# User_Interface.net
KiCad netlist of a schematic drawn in Altium Designer
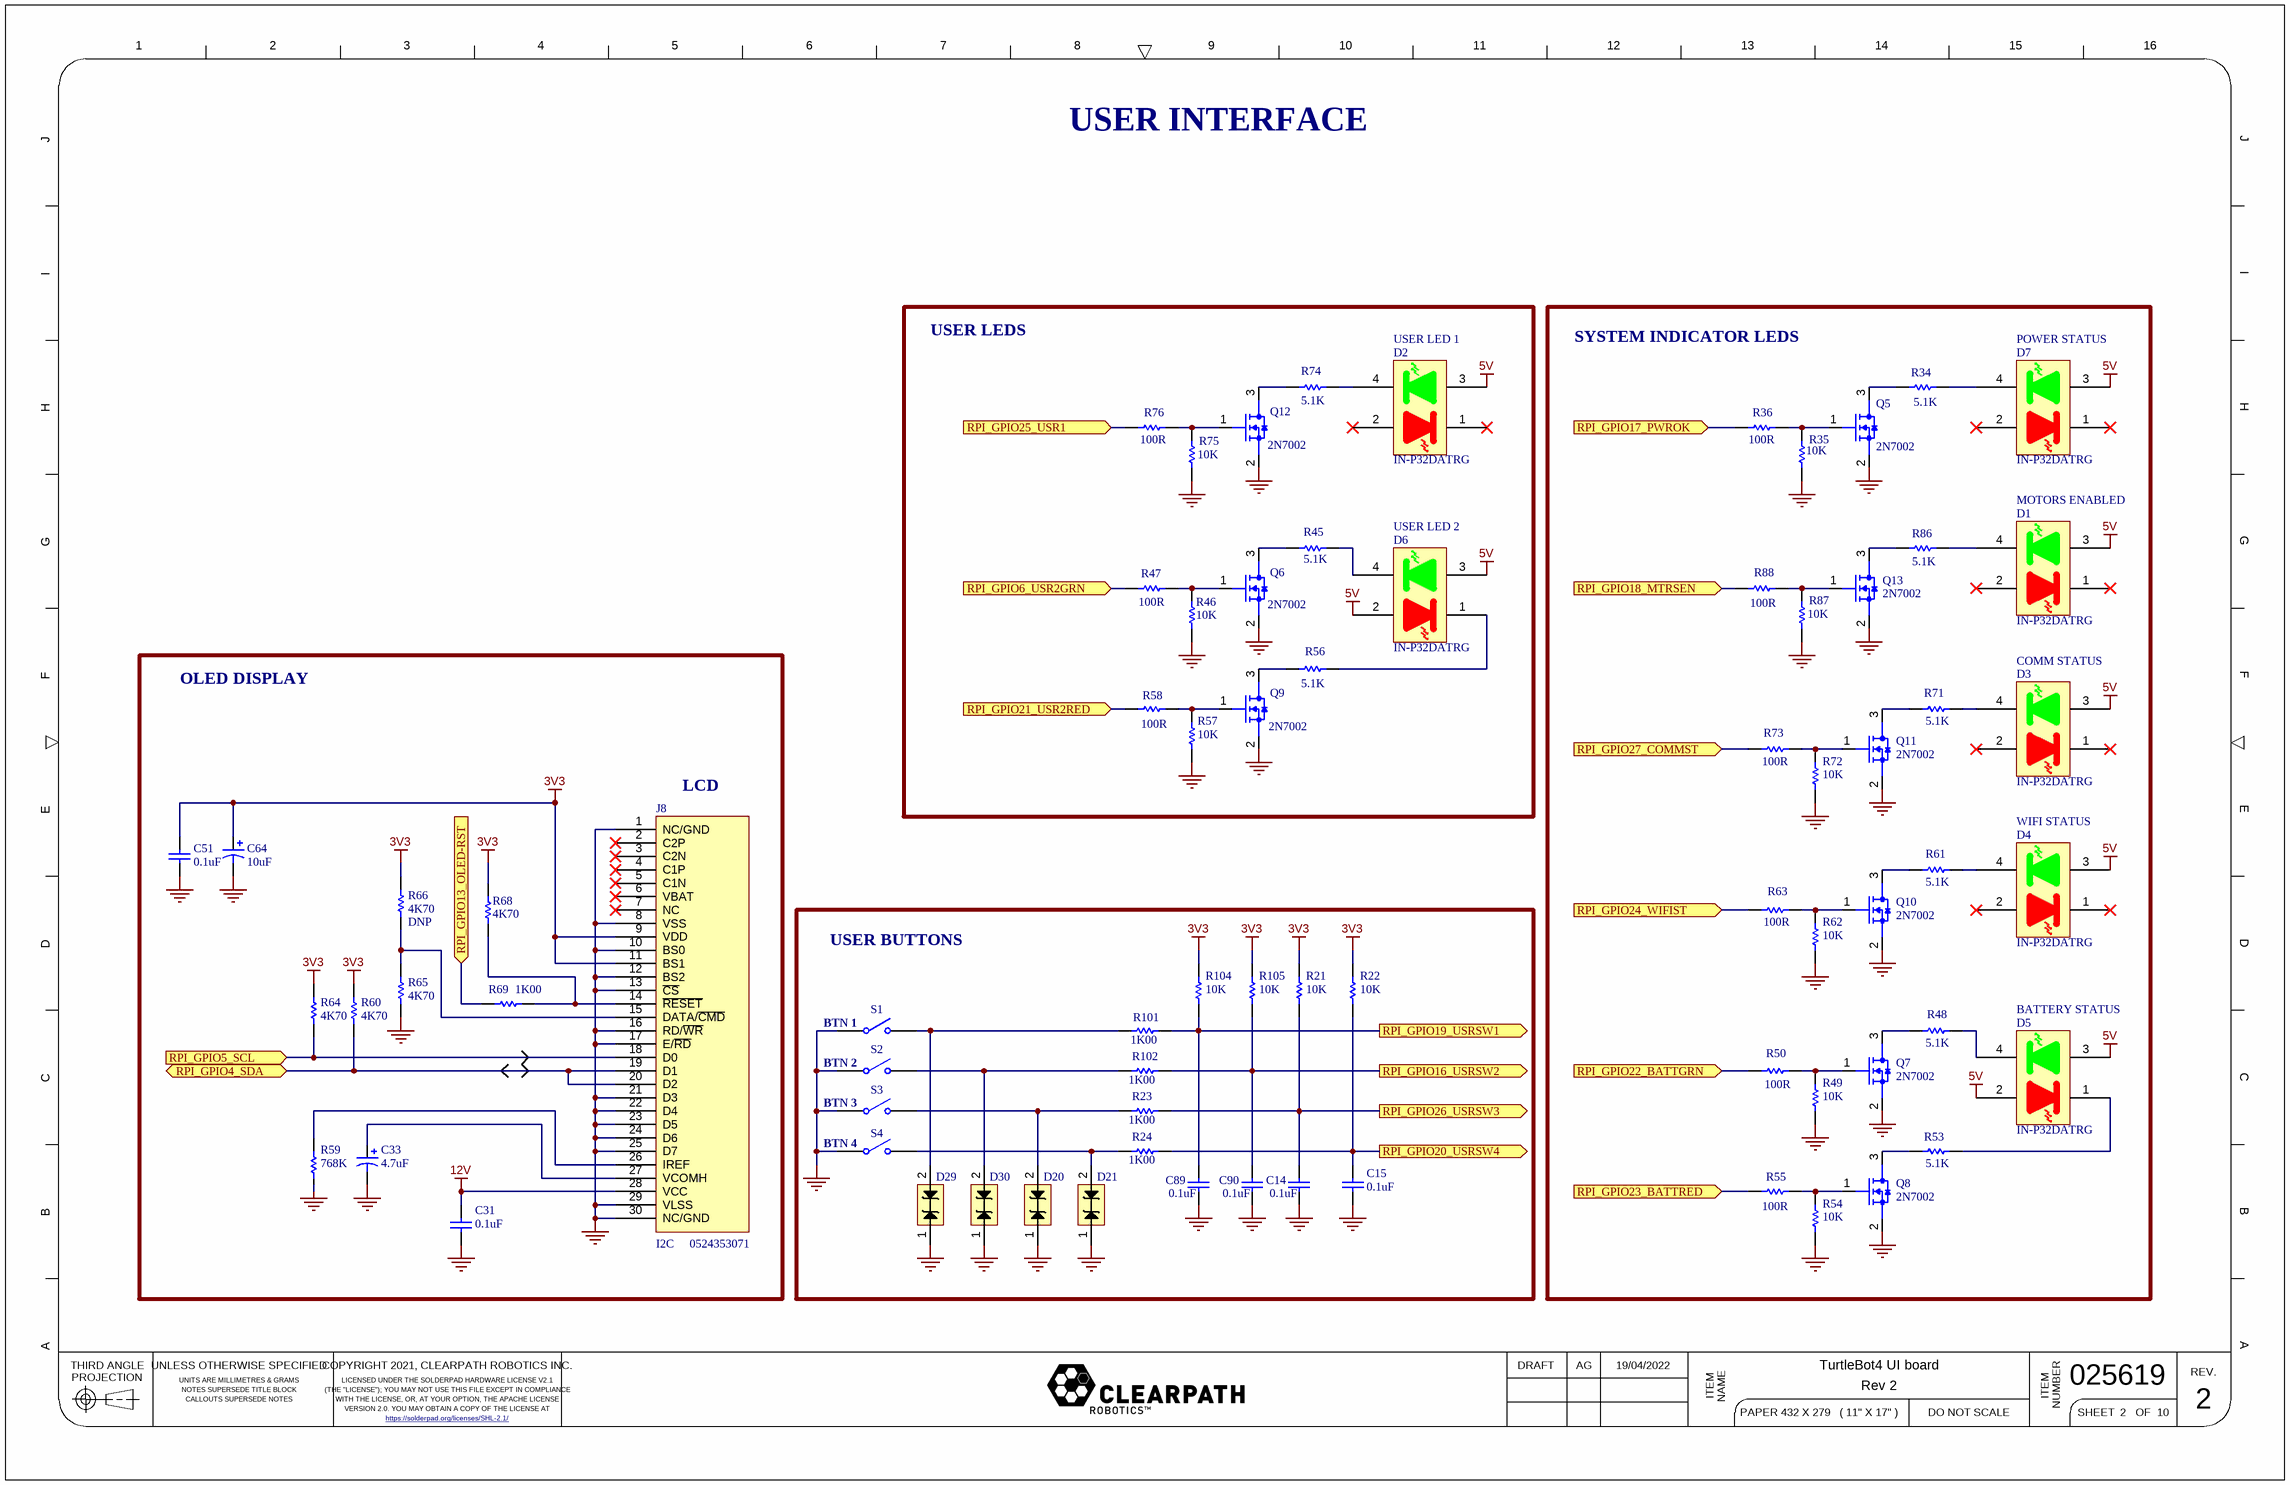
[diagram p0: User Interface.SchDoc]

(export (version "E")
  (design (tool "Eeschema 10.0.6"))
  (components
    (comp (ref "C14")
      (value "0.1uF")
      (footprint "C0805")
      (description "Capacitor")
      (fields (field (name "TOLERANCE") "10%") (field (name "VOLTAGE") "50V"))
      (libsource (lib "CPR_CommonDevices") (part "Capacitor _SMT"))
    )
    (comp (ref "C15")
      (value "0.1uF")
      (footprint "C0805")
      (description "Capacitor")
      (fields (field (name "TOLERANCE") "10%") (field (name "VOLTAGE") "25V"))
      (libsource (lib "CPR_CommonDevices") (part "Capacitor _SMT"))
    )
    (comp (ref "C31")
      (value "0.1uF")
      (footprint "C0805")
      (description "Capacitor")
      (fields (field (name "TOLERANCE") "10%") (field (name "VOLTAGE") "50V"))
      (libsource (lib "CPR_CommonDevices") (part "Capacitor _SMT"))
    )
    (comp (ref "C33")
      (value "4.7uF")
      (footprint "CAP_TANT_3216-18")
      (description "Polarized Capacitor (Radial)")
      (fields (field (name "VOLTAGE") "25V") (field (name "TOLERANCE") "10%"))
      (libsource (lib "Miscellaneous Devices") (part "Cap Pol1"))
    )
    (comp (ref "C51")
      (value "0.1uF")
      (footprint "C0805")
      (description "Capacitor")
      (fields (field (name "TOLERANCE") "10%") (field (name "VOLTAGE") "25V"))
      (libsource (lib "CPR_CommonDevices") (part "Capacitor _SMT"))
    )
    (comp (ref "C64")
      (value "10uF")
      (footprint "CAP_TANT_3216-18")
      (description "Polarized Capacitor (Radial)")
      (fields (field (name "VOLTAGE") "10V") (field (name "TOLERANCE") "10%"))
      (libsource (lib "Miscellaneous Devices") (part "Cap Pol1"))
    )
    (comp (ref "C89")
      (value "0.1uF")
      (footprint "C0805")
      (description "Capacitor")
      (fields (field (name "TOLERANCE") "10%") (field (name "VOLTAGE") "50V"))
      (libsource (lib "CPR_CommonDevices") (part "Capacitor _SMT"))
    )
    (comp (ref "C90")
      (value "0.1uF")
      (footprint "C0805")
      (description "Capacitor")
      (fields (field (name "TOLERANCE") "10%") (field (name "VOLTAGE") "50V"))
      (libsource (lib "CPR_CommonDevices") (part "Capacitor _SMT"))
    )
    (comp (ref "D1")
      (value "MOTORS ENABLED")
      (footprint "IN-P32DATRG")
      (description "Dual Colour LED 3528")
      (fields (field (name "MFG PN") "IN-P32DATRG") (field (name "MFG") "Inolux"))
      (libsource (lib "Inolux IN_P32DATRG RG LED") (part "INOLUX IN_P32DATRG LED"))
    )
    (comp (ref "D2")
      (value "USER LED 1")
      (footprint "IN-P32DATRG")
      (description "Dual Colour LED 3528")
      (fields (field (name "MFG PN") "IN-P32DATRG") (field (name "MFG") "Inolux"))
      (libsource (lib "Inolux IN_P32DATRG RG LED") (part "INOLUX IN_P32DATRG LED"))
    )
    (comp (ref "D3")
      (value "COMM STATUS")
      (footprint "IN-P32DATRG")
      (description "Dual Colour LED 3528")
      (fields (field (name "MFG PN") "IN-P32DATRG") (field (name "MFG") "Inolux"))
      (libsource (lib "Inolux IN_P32DATRG RG LED") (part "INOLUX IN_P32DATRG LED"))
    )
    (comp (ref "D4")
      (value "WIFI STATUS")
      (footprint "IN-P32DATRG")
      (description "Dual Colour LED 3528")
      (fields (field (name "MFG PN") "IN-P32DATRG") (field (name "MFG") "Inolux"))
      (libsource (lib "Inolux IN_P32DATRG RG LED") (part "INOLUX IN_P32DATRG LED"))
    )
    (comp (ref "D5")
      (value "BATTERY STATUS")
      (footprint "IN-P32DATRG")
      (description "Dual Colour LED 3528")
      (fields (field (name "MFG PN") "IN-P32DATRG") (field (name "MFG") "Inolux"))
      (libsource (lib "Inolux IN_P32DATRG RG LED") (part "INOLUX IN_P32DATRG LED"))
    )
    (comp (ref "D6")
      (value "USER LED 2")
      (footprint "IN-P32DATRG")
      (description "Dual Colour LED 3528")
      (fields (field (name "MFG PN") "IN-P32DATRG") (field (name "MFG") "Inolux"))
      (libsource (lib "Inolux IN_P32DATRG RG LED") (part "INOLUX IN_P32DATRG LED"))
    )
    (comp (ref "D7")
      (value "POWER STATUS")
      (footprint "IN-P32DATRG")
      (description "Dual Colour LED 3528")
      (fields (field (name "MFG PN") "IN-P32DATRG") (field (name "MFG") "Inolux"))
      (libsource (lib "Inolux IN_P32DATRG RG LED") (part "INOLUX IN_P32DATRG LED"))
    )
    (comp (ref "D20")
      (value "TVS DIODE BIDIR 15V SMC")
      (footprint "General PCB Library:DO-214AA")
      (description "TVS 600W 15V BI-DIR DO-214AA")
      (fields (field (name "MFG") "Littelfuse Inc."))
      (libsource (lib "SMBJ15CA") (part "TVS DIODE BIDIR 15V SMC"))
    )
    (comp (ref "D21")
      (value "TVS DIODE BIDIR 15V SMC")
      (footprint "General PCB Library:DO-214AA")
      (description "TVS 600W 15V BI-DIR DO-214AA")
      (fields (field (name "MFG") "Littelfuse Inc."))
      (libsource (lib "SMBJ15CA") (part "TVS DIODE BIDIR 15V SMC"))
    )
    (comp (ref "D29")
      (value "TVS DIODE BIDIR 15V SMC")
      (footprint "General PCB Library:DO-214AA")
      (description "TVS 600W 15V BI-DIR DO-214AA")
      (fields (field (name "MFG") "Littelfuse Inc."))
      (libsource (lib "SMBJ15CA") (part "TVS DIODE BIDIR 15V SMC"))
    )
    (comp (ref "D30")
      (value "TVS DIODE BIDIR 15V SMC")
      (footprint "General PCB Library:DO-214AA")
      (description "TVS 600W 15V BI-DIR DO-214AA")
      (fields (field (name "MFG") "Littelfuse Inc."))
      (libsource (lib "SMBJ15CA") (part "TVS DIODE BIDIR 15V SMC"))
    )
    (comp (ref "J8")
      (value "128x64 OLED")
      (footprint "MOLEX_0524353071_REV")
      (description "128x64 OLED module")
      (fields (field (name "MANUFACTURER") "Molex") (field (name "MFG PN") "0524353071"))
      (libsource (lib "ER-OLED013-1") (part "ER-OLED013-1"))
    )
    (comp (ref "Q5")
      (value "NFET")
      (footprint "SOT-23-3")
      (fields (field (name "MFG PN") "2N7002") (field (name "MFG") "ON Semi"))
      (libsource (lib "NFET_SINGLE") (part "NFET_SNGL"))
    )
    (comp (ref "Q6")
      (value "NFET")
      (footprint "SOT-23-3")
      (fields (field (name "MFG PN") "2N7002") (field (name "MFG") "ON Semi"))
      (libsource (lib "NFET_SINGLE") (part "NFET_SNGL"))
    )
    (comp (ref "Q7")
      (value "NFET")
      (footprint "SOT-23-3")
      (fields (field (name "MFG PN") "2N7002") (field (name "MFG") "ON Semi"))
      (libsource (lib "NFET_SINGLE") (part "NFET_SNGL"))
    )
    (comp (ref "Q8")
      (value "NFET")
      (footprint "SOT-23-3")
      (fields (field (name "MFG PN") "2N7002") (field (name "MFG") "ON Semi"))
      (libsource (lib "NFET_SINGLE") (part "NFET_SNGL"))
    )
    (comp (ref "Q9")
      (value "NFET")
      (footprint "SOT-23-3")
      (fields (field (name "MFG PN") "2N7002") (field (name "MFG") "ON Semi"))
      (libsource (lib "NFET_SINGLE") (part "NFET_SNGL"))
    )
    (comp (ref "Q10")
      (value "NFET")
      (footprint "SOT-23-3")
      (fields (field (name "MFG PN") "2N7002") (field (name "MFG") "ON Semi"))
      (libsource (lib "NFET_SINGLE") (part "NFET_SNGL"))
    )
    (comp (ref "Q11")
      (value "NFET")
      (footprint "SOT-23-3")
      (fields (field (name "MFG PN") "2N7002") (field (name "MFG") "ON Semi"))
      (libsource (lib "NFET_SINGLE") (part "NFET_SNGL"))
    )
    (comp (ref "Q12")
      (value "NFET")
      (footprint "SOT-23-3")
      (fields (field (name "MFG PN") "2N7002") (field (name "MFG") "ON Semi"))
      (libsource (lib "NFET_SINGLE") (part "NFET_SNGL"))
    )
    (comp (ref "Q13")
      (value "NFET")
      (footprint "SOT-23-3")
      (fields (field (name "MFG PN") "2N7002") (field (name "MFG") "ON Semi"))
      (libsource (lib "NFET_SINGLE") (part "NFET_SNGL"))
    )
    (comp (ref "R21")
      (value "10K")
      (footprint "R0805")
      (description "Resistor")
      (fields (field (name "TOLERANCE") "1%") (field (name "MFG") "Yageo"))
      (libsource (lib "CPR_CommonDevices") (part "Resistor_SMT"))
    )
    (comp (ref "R22")
      (value "10K")
      (footprint "R0805")
      (description "Resistor")
      (fields (field (name "TOLERANCE") "1%") (field (name "MFG") "Yageo"))
      (libsource (lib "CPR_CommonDevices") (part "Resistor_SMT"))
    )
    (comp (ref "R23")
      (value "1K00")
      (footprint "R0805")
      (description "Resistor")
      (fields (field (name "TOLERANCE") "1%") (field (name "MFG") "Yageo"))
      (libsource (lib "CPR_CommonDevices") (part "Resistor_SMT"))
    )
    (comp (ref "R24")
      (value "1K00")
      (footprint "R0805")
      (description "Resistor")
      (fields (field (name "TOLERANCE") "1%") (field (name "MFG") "Yageo"))
      (libsource (lib "CPR_CommonDevices") (part "Resistor_SMT"))
    )
    (comp (ref "R34")
      (value "5.1K")
      (footprint "R0805")
      (description "Resistor")
      (fields (field (name "TOLERANCE") "1%") (field (name "Comment") "Resistor_SMT"))
      (libsource (lib "CPR_CommonDevices") (part "Resistor_SMT"))
    )
    (comp (ref "R35")
      (value "10K")
      (footprint "R0805")
      (description "Resistor")
      (fields (field (name "TOLERANCE") "1%") (field (name "MFG") "Yageo"))
      (libsource (lib "CPR_CommonDevices") (part "Resistor_SMT"))
    )
    (comp (ref "R36")
      (value "100R")
      (footprint "R0805")
      (description "Resistor")
      (fields (field (name "TOLERANCE") "1%") (field (name "MFG") "Yageo"))
      (libsource (lib "CPR_CommonDevices") (part "Resistor_SMT"))
    )
    (comp (ref "R45")
      (value "5.1K")
      (footprint "R0805")
      (description "Resistor")
      (fields (field (name "TOLERANCE") "1%") (field (name "MFG") "Yageo"))
      (libsource (lib "CPR_CommonDevices") (part "Resistor_SMT"))
    )
    (comp (ref "R46")
      (value "10K")
      (footprint "R0805")
      (description "Resistor")
      (fields (field (name "TOLERANCE") "1%") (field (name "MFG") "Yageo"))
      (libsource (lib "CPR_CommonDevices") (part "Resistor_SMT"))
    )
    (comp (ref "R47")
      (value "100R")
      (footprint "R0805")
      (description "Resistor")
      (fields (field (name "TOLERANCE") "1%") (field (name "MFG") "Yageo"))
      (libsource (lib "CPR_CommonDevices") (part "Resistor_SMT"))
    )
    (comp (ref "R48")
      (value "5.1K")
      (footprint "R0805")
      (description "Resistor")
      (fields (field (name "TOLERANCE") "1%") (field (name "MFG") "Yageo"))
      (libsource (lib "CPR_CommonDevices") (part "Resistor_SMT"))
    )
    (comp (ref "R49")
      (value "10K")
      (footprint "R0805")
      (description "Resistor")
      (fields (field (name "TOLERANCE") "1%") (field (name "MFG") "Yageo"))
      (libsource (lib "CPR_CommonDevices") (part "Resistor_SMT"))
    )
    (comp (ref "R50")
      (value "100R")
      (footprint "R0805")
      (description "Resistor")
      (fields (field (name "TOLERANCE") "1%") (field (name "MFG") "Yageo"))
      (libsource (lib "CPR_CommonDevices") (part "Resistor_SMT"))
    )
    (comp (ref "R53")
      (value "5.1K")
      (footprint "R0805")
      (description "Resistor")
      (fields (field (name "TOLERANCE") "1%") (field (name "MFG") "Yageo"))
      (libsource (lib "CPR_CommonDevices") (part "Resistor_SMT"))
    )
    (comp (ref "R54")
      (value "10K")
      (footprint "R0805")
      (description "Resistor")
      (fields (field (name "TOLERANCE") "1%") (field (name "MFG") "Yageo"))
      (libsource (lib "CPR_CommonDevices") (part "Resistor_SMT"))
    )
    (comp (ref "R55")
      (value "100R")
      (footprint "R0805")
      (description "Resistor")
      (fields (field (name "TOLERANCE") "1%") (field (name "MFG") "Yageo"))
      (libsource (lib "CPR_CommonDevices") (part "Resistor_SMT"))
    )
    (comp (ref "R56")
      (value "5.1K")
      (footprint "R0805")
      (description "Resistor")
      (fields (field (name "TOLERANCE") "1%") (field (name "MFG") "Yageo"))
      (libsource (lib "CPR_CommonDevices") (part "Resistor_SMT"))
    )
    (comp (ref "R57")
      (value "10K")
      (footprint "R0805")
      (description "Resistor")
      (fields (field (name "TOLERANCE") "1%") (field (name "MFG") "Yageo"))
      (libsource (lib "CPR_CommonDevices") (part "Resistor_SMT"))
    )
    (comp (ref "R58")
      (value "100R")
      (footprint "R0805")
      (description "Resistor")
      (fields (field (name "TOLERANCE") "1%") (field (name "MFG") "Yageo"))
      (libsource (lib "CPR_CommonDevices") (part "Resistor_SMT"))
    )
    (comp (ref "R59")
      (value "768K")
      (footprint "R0805")
      (description "Resistor")
      (fields (field (name "TOLERANCE") "1%") (field (name "MFG") "Yageo"))
      (libsource (lib "CPR_CommonDevices") (part "Resistor_SMT"))
    )
    (comp (ref "R60")
      (value "4K70")
      (footprint "R0805")
      (description "Resistor")
      (fields (field (name "TOLERANCE") "1%") (field (name "MFG") "Yageo"))
      (libsource (lib "CPR_CommonDevices") (part "Resistor_SMT"))
    )
    (comp (ref "R61")
      (value "5.1K")
      (footprint "R0805")
      (description "Resistor")
      (fields (field (name "TOLERANCE") "1%") (field (name "MFG") "Yageo"))
      (libsource (lib "CPR_CommonDevices") (part "Resistor_SMT"))
    )
    (comp (ref "R62")
      (value "10K")
      (footprint "R0805")
      (description "Resistor")
      (fields (field (name "TOLERANCE") "1%") (field (name "MFG") "Yageo"))
      (libsource (lib "CPR_CommonDevices") (part "Resistor_SMT"))
    )
    (comp (ref "R63")
      (value "100R")
      (footprint "R0805")
      (description "Resistor")
      (fields (field (name "TOLERANCE") "1%") (field (name "MFG") "Yageo"))
      (libsource (lib "CPR_CommonDevices") (part "Resistor_SMT"))
    )
    (comp (ref "R64")
      (value "4K70")
      (footprint "R0805")
      (description "Resistor")
      (fields (field (name "TOLERANCE") "1%") (field (name "MFG") "Yageo"))
      (libsource (lib "CPR_CommonDevices") (part "Resistor_SMT"))
    )
    (comp (ref "R65")
      (value "4K70")
      (footprint "R0805")
      (description "Resistor")
      (fields (field (name "TOLERANCE") "1%") (field (name "MFG") "Yageo"))
      (libsource (lib "CPR_CommonDevices") (part "Resistor_SMT"))
    )
    (comp (ref "R66")
      (value "4K70")
      (footprint "R0805")
      (description "Resistor")
      (fields (field (name "TOLERANCE") "1%") (field (name "DNP") "DNP") (field (name "MFG") "Yageo"))
      (libsource (lib "CPR_CommonDevices") (part "Resistor_SMT"))
    )
    (comp (ref "R68")
      (value "4K70")
      (footprint "R0805")
      (description "Resistor")
      (fields (field (name "TOLERANCE") "1%") (field (name "MFG") "Yageo"))
      (libsource (lib "CPR_CommonDevices") (part "Resistor_SMT"))
    )
    (comp (ref "R69")
      (value "1K00")
      (footprint "R0805")
      (description "Resistor")
      (fields (field (name "TOLERANCE") "1%") (field (name "MFG") "Yageo"))
      (libsource (lib "CPR_CommonDevices") (part "Resistor_SMT"))
    )
    (comp (ref "R71")
      (value "5.1K")
      (footprint "R0805")
      (description "Resistor")
      (fields (field (name "TOLERANCE") "1%") (field (name "MFG") "Yageo"))
      (libsource (lib "CPR_CommonDevices") (part "Resistor_SMT"))
    )
    (comp (ref "R72")
      (value "10K")
      (footprint "R0805")
      (description "Resistor")
      (fields (field (name "TOLERANCE") "1%") (field (name "MFG") "Yageo"))
      (libsource (lib "CPR_CommonDevices") (part "Resistor_SMT"))
    )
    (comp (ref "R73")
      (value "100R")
      (footprint "R0805")
      (description "Resistor")
      (fields (field (name "TOLERANCE") "1%") (field (name "MFG") "Yageo"))
      (libsource (lib "CPR_CommonDevices") (part "Resistor_SMT"))
    )
    (comp (ref "R74")
      (value "5.1K")
      (footprint "R0805")
      (description "Resistor")
      (fields (field (name "TOLERANCE") "1%") (field (name "MFG") "Yageo"))
      (libsource (lib "CPR_CommonDevices") (part "Resistor_SMT"))
    )
    (comp (ref "R75")
      (value "10K")
      (footprint "R0805")
      (description "Resistor")
      (fields (field (name "TOLERANCE") "1%") (field (name "MFG") "Yageo"))
      (libsource (lib "CPR_CommonDevices") (part "Resistor_SMT"))
    )
    (comp (ref "R76")
      (value "100R")
      (footprint "R0805")
      (description "Resistor")
      (fields (field (name "TOLERANCE") "1%") (field (name "MFG") "Yageo"))
      (libsource (lib "CPR_CommonDevices") (part "Resistor_SMT"))
    )
    (comp (ref "R86")
      (value "5.1K")
      (footprint "R0805")
      (description "Resistor")
      (fields (field (name "TOLERANCE") "1%") (field (name "MFG") "Yageo"))
      (libsource (lib "CPR_CommonDevices") (part "Resistor_SMT"))
    )
    (comp (ref "R87")
      (value "10K")
      (footprint "R0805")
      (description "Resistor")
      (fields (field (name "TOLERANCE") "1%") (field (name "MFG") "Yageo"))
      (libsource (lib "CPR_CommonDevices") (part "Resistor_SMT"))
    )
    (comp (ref "R88")
      (value "100R")
      (footprint "R0805")
      (description "Resistor")
      (fields (field (name "TOLERANCE") "1%") (field (name "MFG") "Yageo"))
      (libsource (lib "CPR_CommonDevices") (part "Resistor_SMT"))
    )
    (comp (ref "R101")
      (value "1K00")
      (footprint "R0805")
      (description "Resistor")
      (fields (field (name "TOLERANCE") "1%") (field (name "MFG") "Yageo"))
      (libsource (lib "CPR_CommonDevices") (part "Resistor_SMT"))
    )
    (comp (ref "R102")
      (value "1K00")
      (footprint "R0805")
      (description "Resistor")
      (fields (field (name "TOLERANCE") "1%") (field (name "MFG") "Yageo"))
      (libsource (lib "CPR_CommonDevices") (part "Resistor_SMT"))
    )
    (comp (ref "R104")
      (value "10K")
      (footprint "R0805")
      (description "Resistor")
      (fields (field (name "TOLERANCE") "1%") (field (name "MFG") "Yageo"))
      (libsource (lib "CPR_CommonDevices") (part "Resistor_SMT"))
    )
    (comp (ref "R105")
      (value "10K")
      (footprint "R0805")
      (description "Resistor")
      (fields (field (name "TOLERANCE") "1%") (field (name "MFG") "Yageo"))
      (libsource (lib "CPR_CommonDevices") (part "Resistor_SMT"))
    )
    (comp (ref "S1")
      (value "SW-SPST")
      (footprint "PANA_EVP-ASKC1A")
      (description "Single-Pole, Single-Throw Switch")
      (fields (field (name "MFG") "Panasonic"))
      (libsource (lib "Miscellaneous Devices") (part "SW-SPST"))
    )
    (comp (ref "S2")
      (value "SW-SPST")
      (footprint "PANA_EVP-ASKC1A")
      (description "Single-Pole, Single-Throw Switch")
      (fields (field (name "MFG") "Panasonic"))
      (libsource (lib "Miscellaneous Devices") (part "SW-SPST"))
    )
    (comp (ref "S3")
      (value "SW-SPST")
      (footprint "PANA_EVP-ASKC1A")
      (description "Single-Pole, Single-Throw Switch")
      (fields (field (name "MFG") "Panasonic"))
      (libsource (lib "Miscellaneous Devices") (part "SW-SPST"))
    )
    (comp (ref "S4")
      (value "SW-SPST")
      (footprint "PANA_EVP-ASKC1A")
      (description "Single-Pole, Single-Throw Switch")
      (fields (field (name "MFG") "Panasonic"))
      (libsource (lib "Miscellaneous Devices") (part "SW-SPST"))
    )
  )
  (nets
    (net (code "1") (name "/RPI_GPIO4_SDA") (class "Default")
      (node (ref "J8") (pin "19") (pinfunction "D1_19") (pintype "passive"))
      (node (ref "J8") (pin "20") (pinfunction "D2_20") (pintype "passive"))
      (node (ref "R60") (pin "2") (pinfunction "2_2") (pintype "passive"))
    )
    (net (code "2") (name "/RPI_GPIO5_SCL") (class "Default")
      (node (ref "J8") (pin "18") (pinfunction "D0_18") (pintype "passive"))
      (node (ref "R64") (pin "2") (pinfunction "2_2") (pintype "passive"))
    )
    (net (code "3") (name "/RPI_GPIO6_USR2GRN") (class "Default")
      (node (ref "R47") (pin "2") (pinfunction "2_2") (pintype "passive"))
    )
    (net (code "4") (name "/RPI_GPIO13_OLED-RST") (class "Default")
      (node (ref "R69") (pin "1") (pinfunction "1_1") (pintype "passive"))
    )
    (net (code "5") (name "/RPI_GPIO16_USRSW2") (class "Default")
      (node (ref "C90") (pin "2") (pinfunction "2_2") (pintype "passive"))
      (node (ref "R102") (pin "1") (pinfunction "1_1") (pintype "passive"))
      (node (ref "R105") (pin "2") (pinfunction "2_2") (pintype "passive"))
    )
    (net (code "6") (name "/RPI_GPIO17_PWROK") (class "Default")
      (node (ref "R36") (pin "2") (pinfunction "2_2") (pintype "passive"))
    )
    (net (code "7") (name "/RPI_GPIO18_MTRSEN") (class "Default")
      (node (ref "R88") (pin "2") (pinfunction "2_2") (pintype "passive"))
    )
    (net (code "8") (name "/RPI_GPIO19_USRSW1") (class "Default")
      (node (ref "C89") (pin "2") (pinfunction "2_2") (pintype "passive"))
      (node (ref "R101") (pin "1") (pinfunction "1_1") (pintype "passive"))
      (node (ref "R104") (pin "2") (pinfunction "2_2") (pintype "passive"))
    )
    (net (code "9") (name "/RPI_GPIO20_USRSW4") (class "Default")
      (node (ref "C15") (pin "2") (pinfunction "2_2") (pintype "passive"))
      (node (ref "R22") (pin "2") (pinfunction "2_2") (pintype "passive"))
      (node (ref "R24") (pin "1") (pinfunction "1_1") (pintype "passive"))
    )
    (net (code "10") (name "/RPI_GPIO21_USR2RED") (class "Default")
      (node (ref "R58") (pin "2") (pinfunction "2_2") (pintype "passive"))
    )
    (net (code "11") (name "/RPI_GPIO22_BATTGRN") (class "Default")
      (node (ref "R50") (pin "2") (pinfunction "2_2") (pintype "passive"))
    )
    (net (code "12") (name "/RPI_GPIO23_BATTRED") (class "Default")
      (node (ref "R55") (pin "2") (pinfunction "2_2") (pintype "passive"))
    )
    (net (code "13") (name "/RPI_GPIO24_WIFIST") (class "Default")
      (node (ref "R63") (pin "2") (pinfunction "2_2") (pintype "passive"))
    )
    (net (code "14") (name "/RPI_GPIO25_USR1") (class "Default")
      (node (ref "R76") (pin "2") (pinfunction "2_2") (pintype "passive"))
    )
    (net (code "15") (name "/RPI_GPIO26_USRSW3") (class "Default")
      (node (ref "C14") (pin "2") (pinfunction "2_2") (pintype "passive"))
      (node (ref "R21") (pin "2") (pinfunction "2_2") (pintype "passive"))
      (node (ref "R23") (pin "1") (pinfunction "1_1") (pintype "passive"))
    )
    (net (code "16") (name "/RPI_GPIO27_COMMST") (class "Default")
      (node (ref "R73") (pin "2") (pinfunction "2_2") (pintype "passive"))
    )
    (net (code "17") (name "3V3") (class "Default")
      (node (ref "C51") (pin "2") (pinfunction "2_2") (pintype "passive"))
      (node (ref "C64") (pin "1") (pinfunction "1_1") (pintype "passive"))
      (node (ref "J8") (pin "11") (pinfunction "BS1_11") (pintype "passive"))
      (node (ref "J8") (pin "9") (pinfunction "VDD_9") (pintype "passive"))
      (node (ref "R104") (pin "1") (pinfunction "1_1") (pintype "passive"))
      (node (ref "R105") (pin "1") (pinfunction "1_1") (pintype "passive"))
      (node (ref "R21") (pin "1") (pinfunction "1_1") (pintype "passive"))
      (node (ref "R22") (pin "1") (pinfunction "1_1") (pintype "passive"))
      (node (ref "R60") (pin "1") (pinfunction "1_1") (pintype "passive"))
      (node (ref "R64") (pin "1") (pinfunction "1_1") (pintype "passive"))
      (node (ref "R66") (pin "1") (pinfunction "1_1") (pintype "passive"))
      (node (ref "R68") (pin "1") (pinfunction "1_1") (pintype "passive"))
    )
    (net (code "18") (name "5V") (class "Default")
      (node (ref "D1") (pin "3") (pinfunction "GA_3") (pintype "passive"))
      (node (ref "D2") (pin "3") (pinfunction "GA_3") (pintype "passive"))
      (node (ref "D3") (pin "3") (pinfunction "GA_3") (pintype "passive"))
      (node (ref "D4") (pin "3") (pinfunction "GA_3") (pintype "passive"))
      (node (ref "D5") (pin "2") (pinfunction "RA_2") (pintype "passive"))
      (node (ref "D5") (pin "3") (pinfunction "GA_3") (pintype "passive"))
      (node (ref "D6") (pin "2") (pinfunction "RA_2") (pintype "passive"))
      (node (ref "D6") (pin "3") (pinfunction "GA_3") (pintype "passive"))
      (node (ref "D7") (pin "3") (pinfunction "GA_3") (pintype "passive"))
    )
    (net (code "19") (name "12V") (class "Default")
      (node (ref "C31") (pin "2") (pinfunction "2_2") (pintype "passive"))
      (node (ref "J8") (pin "28") (pinfunction "VCC_28") (pintype "passive"))
    )
    (net (code "20") (name "GND") (class "Default")
      (node (ref "C14") (pin "1") (pinfunction "1_1") (pintype "passive"))
      (node (ref "C15") (pin "1") (pinfunction "1_1") (pintype "passive"))
      (node (ref "C31") (pin "1") (pinfunction "1_1") (pintype "passive"))
      (node (ref "C33") (pin "2") (pinfunction "2_2") (pintype "passive"))
      (node (ref "C51") (pin "1") (pinfunction "1_1") (pintype "passive"))
      (node (ref "C64") (pin "2") (pinfunction "2_2") (pintype "passive"))
      (node (ref "C89") (pin "1") (pinfunction "1_1") (pintype "passive"))
      (node (ref "C90") (pin "1") (pinfunction "1_1") (pintype "passive"))
      (node (ref "D20") (pin "1") (pintype "passive"))
      (node (ref "D21") (pin "1") (pintype "passive"))
      (node (ref "D29") (pin "1") (pintype "passive"))
      (node (ref "D30") (pin "1") (pintype "passive"))
      (node (ref "J8") (pin "1") (pinfunction "NC/GND_1") (pintype "passive"))
      (node (ref "J8") (pin "10") (pinfunction "BS0_10") (pintype "passive"))
      (node (ref "J8") (pin "12") (pinfunction "BS2_12") (pintype "passive"))
      (node (ref "J8") (pin "13") (pinfunction "~{CS}_13") (pintype "passive"))
      (node (ref "J8") (pin "16") (pinfunction "RD/~{WR}_16") (pintype "passive"))
      (node (ref "J8") (pin "17") (pinfunction "E/~{RD}_17") (pintype "passive"))
      (node (ref "J8") (pin "21") (pinfunction "D3_21") (pintype "passive"))
      (node (ref "J8") (pin "22") (pinfunction "D4_22") (pintype "passive"))
      (node (ref "J8") (pin "23") (pinfunction "D5_23") (pintype "passive"))
      (node (ref "J8") (pin "24") (pinfunction "D6_24") (pintype "passive"))
      (node (ref "J8") (pin "25") (pinfunction "D7_25") (pintype "passive"))
      (node (ref "J8") (pin "29") (pinfunction "VLSS_29") (pintype "passive"))
      (node (ref "J8") (pin "30") (pinfunction "NC/GND_30") (pintype "passive"))
      (node (ref "J8") (pin "8") (pinfunction "VSS_8") (pintype "passive"))
      (node (ref "Q10") (pin "2") (pinfunction "D1_2") (pintype "passive"))
      (node (ref "Q11") (pin "2") (pinfunction "D1_2") (pintype "passive"))
      (node (ref "Q12") (pin "2") (pinfunction "D1_2") (pintype "passive"))
      (node (ref "Q13") (pin "2") (pinfunction "D1_2") (pintype "passive"))
      (node (ref "Q5") (pin "2") (pinfunction "D1_2") (pintype "passive"))
      (node (ref "Q6") (pin "2") (pinfunction "D1_2") (pintype "passive"))
      (node (ref "Q7") (pin "2") (pinfunction "D1_2") (pintype "passive"))
      (node (ref "Q8") (pin "2") (pinfunction "D1_2") (pintype "passive"))
      (node (ref "Q9") (pin "2") (pinfunction "D1_2") (pintype "passive"))
      (node (ref "R35") (pin "2") (pinfunction "2_2") (pintype "passive"))
      (node (ref "R46") (pin "2") (pinfunction "2_2") (pintype "passive"))
      (node (ref "R49") (pin "2") (pinfunction "2_2") (pintype "passive"))
      (node (ref "R54") (pin "2") (pinfunction "2_2") (pintype "passive"))
      (node (ref "R57") (pin "2") (pinfunction "2_2") (pintype "passive"))
      (node (ref "R59") (pin "2") (pinfunction "2_2") (pintype "passive"))
      (node (ref "R62") (pin "2") (pinfunction "2_2") (pintype "passive"))
      (node (ref "R65") (pin "2") (pinfunction "2_2") (pintype "passive"))
      (node (ref "R72") (pin "2") (pinfunction "2_2") (pintype "passive"))
      (node (ref "R75") (pin "2") (pinfunction "2_2") (pintype "passive"))
      (node (ref "R87") (pin "2") (pinfunction "2_2") (pintype "passive"))
      (node (ref "S1") (pin "1") (pinfunction "COMMON_1") (pintype "passive"))
      (node (ref "S2") (pin "1") (pinfunction "COMMON_1") (pintype "passive"))
      (node (ref "S3") (pin "1") (pinfunction "COMMON_1") (pintype "passive"))
      (node (ref "S4") (pin "1") (pinfunction "COMMON_1") (pintype "passive"))
    )
    (net (code "21") (name "Net-(D1-GK)") (class "Default")
      (node (ref "D1") (pin "4") (pinfunction "GK_4") (pintype "passive"))
      (node (ref "R86") (pin "1") (pinfunction "1_1") (pintype "passive"))
    )
    (net (code "22") (name "Net-(D2-GK)") (class "Default")
      (node (ref "D2") (pin "4") (pinfunction "GK_4") (pintype "passive"))
      (node (ref "R74") (pin "1") (pinfunction "1_1") (pintype "passive"))
    )
    (net (code "23") (name "Net-(D3-GK)") (class "Default")
      (node (ref "D3") (pin "4") (pinfunction "GK_4") (pintype "passive"))
      (node (ref "R71") (pin "1") (pinfunction "1_1") (pintype "passive"))
    )
    (net (code "24") (name "Net-(D4-GK)") (class "Default")
      (node (ref "D4") (pin "4") (pinfunction "GK_4") (pintype "passive"))
      (node (ref "R61") (pin "1") (pinfunction "1_1") (pintype "passive"))
    )
    (net (code "25") (name "Net-(D5-GK)") (class "Default")
      (node (ref "D5") (pin "4") (pinfunction "GK_4") (pintype "passive"))
      (node (ref "R48") (pin "1") (pinfunction "1_1") (pintype "passive"))
    )
    (net (code "26") (name "Net-(D5-RK)") (class "Default")
      (node (ref "D5") (pin "1") (pinfunction "RK_1") (pintype "passive"))
      (node (ref "R53") (pin "1") (pinfunction "1_1") (pintype "passive"))
    )
    (net (code "27") (name "Net-(D6-GK)") (class "Default")
      (node (ref "D6") (pin "4") (pinfunction "GK_4") (pintype "passive"))
      (node (ref "R45") (pin "1") (pinfunction "1_1") (pintype "passive"))
    )
    (net (code "28") (name "Net-(D6-RK)") (class "Default")
      (node (ref "D6") (pin "1") (pinfunction "RK_1") (pintype "passive"))
      (node (ref "R56") (pin "1") (pinfunction "1_1") (pintype "passive"))
    )
    (net (code "29") (name "Net-(D7-GK)") (class "Default")
      (node (ref "D7") (pin "4") (pinfunction "GK_4") (pintype "passive"))
      (node (ref "R34") (pin "1") (pinfunction "1_1") (pintype "passive"))
    )
    (net (code "30") (name "Net-(J8-DATA{slash}~{CMD})") (class "Default")
      (node (ref "J8") (pin "15") (pinfunction "DATA/~{CMD}_15") (pintype "passive"))
      (node (ref "R65") (pin "1") (pinfunction "1_1") (pintype "passive"))
      (node (ref "R66") (pin "2") (pinfunction "2_2") (pintype "passive"))
    )
    (net (code "31") (name "Net-(J8-IREF)") (class "Default")
      (node (ref "J8") (pin "26") (pinfunction "IREF_26") (pintype "passive"))
      (node (ref "R59") (pin "1") (pinfunction "1_1") (pintype "passive"))
    )
    (net (code "32") (name "Net-(J8-VCOMH)") (class "Default")
      (node (ref "C33") (pin "1") (pinfunction "1_1") (pintype "passive"))
      (node (ref "J8") (pin "27") (pinfunction "VCOMH_27") (pintype "passive"))
    )
    (net (code "33") (name "Net-(J8-~{RESET})") (class "Default")
      (node (ref "J8") (pin "14") (pinfunction "~{RESET}_14") (pintype "passive"))
      (node (ref "R68") (pin "2") (pinfunction "2_2") (pintype "passive"))
      (node (ref "R69") (pin "2") (pinfunction "2_2") (pintype "passive"))
    )
    (net (code "34") (name "Net-(Q5-G1)") (class "Default")
      (node (ref "Q5") (pin "1") (pinfunction "G1_1") (pintype "passive"))
      (node (ref "R35") (pin "1") (pinfunction "1_1") (pintype "passive"))
      (node (ref "R36") (pin "1") (pinfunction "1_1") (pintype "passive"))
    )
    (net (code "35") (name "Net-(Q5-S1)") (class "Default")
      (node (ref "Q5") (pin "3") (pinfunction "S1_3") (pintype "passive"))
      (node (ref "R34") (pin "2") (pinfunction "2_2") (pintype "passive"))
    )
    (net (code "36") (name "Net-(Q6-G1)") (class "Default")
      (node (ref "Q6") (pin "1") (pinfunction "G1_1") (pintype "passive"))
      (node (ref "R46") (pin "1") (pinfunction "1_1") (pintype "passive"))
      (node (ref "R47") (pin "1") (pinfunction "1_1") (pintype "passive"))
    )
    (net (code "37") (name "Net-(Q6-S1)") (class "Default")
      (node (ref "Q6") (pin "3") (pinfunction "S1_3") (pintype "passive"))
      (node (ref "R45") (pin "2") (pinfunction "2_2") (pintype "passive"))
    )
    (net (code "38") (name "Net-(Q7-G1)") (class "Default")
      (node (ref "Q7") (pin "1") (pinfunction "G1_1") (pintype "passive"))
      (node (ref "R49") (pin "1") (pinfunction "1_1") (pintype "passive"))
      (node (ref "R50") (pin "1") (pinfunction "1_1") (pintype "passive"))
    )
    (net (code "39") (name "Net-(Q7-S1)") (class "Default")
      (node (ref "Q7") (pin "3") (pinfunction "S1_3") (pintype "passive"))
      (node (ref "R48") (pin "2") (pinfunction "2_2") (pintype "passive"))
    )
    (net (code "40") (name "Net-(Q8-G1)") (class "Default")
      (node (ref "Q8") (pin "1") (pinfunction "G1_1") (pintype "passive"))
      (node (ref "R54") (pin "1") (pinfunction "1_1") (pintype "passive"))
      (node (ref "R55") (pin "1") (pinfunction "1_1") (pintype "passive"))
    )
    (net (code "41") (name "Net-(Q8-S1)") (class "Default")
      (node (ref "Q8") (pin "3") (pinfunction "S1_3") (pintype "passive"))
      (node (ref "R53") (pin "2") (pinfunction "2_2") (pintype "passive"))
    )
    (net (code "42") (name "Net-(Q9-G1)") (class "Default")
      (node (ref "Q9") (pin "1") (pinfunction "G1_1") (pintype "passive"))
      (node (ref "R57") (pin "1") (pinfunction "1_1") (pintype "passive"))
      (node (ref "R58") (pin "1") (pinfunction "1_1") (pintype "passive"))
    )
    (net (code "43") (name "Net-(Q9-S1)") (class "Default")
      (node (ref "Q9") (pin "3") (pinfunction "S1_3") (pintype "passive"))
      (node (ref "R56") (pin "2") (pinfunction "2_2") (pintype "passive"))
    )
    (net (code "44") (name "Net-(Q10-G1)") (class "Default")
      (node (ref "Q10") (pin "1") (pinfunction "G1_1") (pintype "passive"))
      (node (ref "R62") (pin "1") (pinfunction "1_1") (pintype "passive"))
      (node (ref "R63") (pin "1") (pinfunction "1_1") (pintype "passive"))
    )
    (net (code "45") (name "Net-(Q10-S1)") (class "Default")
      (node (ref "Q10") (pin "3") (pinfunction "S1_3") (pintype "passive"))
      (node (ref "R61") (pin "2") (pinfunction "2_2") (pintype "passive"))
    )
    (net (code "46") (name "Net-(Q11-G1)") (class "Default")
      (node (ref "Q11") (pin "1") (pinfunction "G1_1") (pintype "passive"))
      (node (ref "R72") (pin "1") (pinfunction "1_1") (pintype "passive"))
      (node (ref "R73") (pin "1") (pinfunction "1_1") (pintype "passive"))
    )
    (net (code "47") (name "Net-(Q11-S1)") (class "Default")
      (node (ref "Q11") (pin "3") (pinfunction "S1_3") (pintype "passive"))
      (node (ref "R71") (pin "2") (pinfunction "2_2") (pintype "passive"))
    )
    (net (code "48") (name "Net-(Q12-G1)") (class "Default")
      (node (ref "Q12") (pin "1") (pinfunction "G1_1") (pintype "passive"))
      (node (ref "R75") (pin "1") (pinfunction "1_1") (pintype "passive"))
      (node (ref "R76") (pin "1") (pinfunction "1_1") (pintype "passive"))
    )
    (net (code "49") (name "Net-(Q12-S1)") (class "Default")
      (node (ref "Q12") (pin "3") (pinfunction "S1_3") (pintype "passive"))
      (node (ref "R74") (pin "2") (pinfunction "2_2") (pintype "passive"))
    )
    (net (code "50") (name "Net-(Q13-G1)") (class "Default")
      (node (ref "Q13") (pin "1") (pinfunction "G1_1") (pintype "passive"))
      (node (ref "R87") (pin "1") (pinfunction "1_1") (pintype "passive"))
      (node (ref "R88") (pin "1") (pinfunction "1_1") (pintype "passive"))
    )
    (net (code "51") (name "Net-(Q13-S1)") (class "Default")
      (node (ref "Q13") (pin "3") (pinfunction "S1_3") (pintype "passive"))
      (node (ref "R86") (pin "2") (pinfunction "2_2") (pintype "passive"))
    )
    (net (code "52") (name "Net-(S1-NO)") (class "Default")
      (node (ref "D29") (pin "2") (pintype "passive"))
      (node (ref "R101") (pin "2") (pinfunction "2_2") (pintype "passive"))
      (node (ref "S1") (pin "2") (pinfunction "NO_2") (pintype "passive"))
    )
    (net (code "53") (name "Net-(S2-NO)") (class "Default")
      (node (ref "D30") (pin "2") (pintype "passive"))
      (node (ref "R102") (pin "2") (pinfunction "2_2") (pintype "passive"))
      (node (ref "S2") (pin "2") (pinfunction "NO_2") (pintype "passive"))
    )
    (net (code "54") (name "Net-(S3-NO)") (class "Default")
      (node (ref "D20") (pin "2") (pintype "passive"))
      (node (ref "R23") (pin "2") (pinfunction "2_2") (pintype "passive"))
      (node (ref "S3") (pin "2") (pinfunction "NO_2") (pintype "passive"))
    )
    (net (code "55") (name "Net-(S4-NO)") (class "Default")
      (node (ref "D21") (pin "2") (pintype "passive"))
      (node (ref "R24") (pin "2") (pinfunction "2_2") (pintype "passive"))
      (node (ref "S4") (pin "2") (pinfunction "NO_2") (pintype "passive"))
    )
    (net (code "56") (name "unconnected-(D1-RA-Pad2)") (class "Default")
      (node (ref "D1") (pin "2") (pinfunction "RA_2") (pintype "passive+no_connect"))
    )
    (net (code "57") (name "unconnected-(D1-RK-Pad1)") (class "Default")
      (node (ref "D1") (pin "1") (pinfunction "RK_1") (pintype "passive+no_connect"))
    )
    (net (code "58") (name "unconnected-(D2-RA-Pad2)") (class "Default")
      (node (ref "D2") (pin "2") (pinfunction "RA_2") (pintype "passive+no_connect"))
    )
    (net (code "59") (name "unconnected-(D2-RK-Pad1)") (class "Default")
      (node (ref "D2") (pin "1") (pinfunction "RK_1") (pintype "passive+no_connect"))
    )
    (net (code "60") (name "unconnected-(D3-RA-Pad2)") (class "Default")
      (node (ref "D3") (pin "2") (pinfunction "RA_2") (pintype "passive+no_connect"))
    )
    (net (code "61") (name "unconnected-(D3-RK-Pad1)") (class "Default")
      (node (ref "D3") (pin "1") (pinfunction "RK_1") (pintype "passive+no_connect"))
    )
    (net (code "62") (name "unconnected-(D4-RA-Pad2)") (class "Default")
      (node (ref "D4") (pin "2") (pinfunction "RA_2") (pintype "passive+no_connect"))
    )
    (net (code "63") (name "unconnected-(D4-RK-Pad1)") (class "Default")
      (node (ref "D4") (pin "1") (pinfunction "RK_1") (pintype "passive+no_connect"))
    )
    (net (code "64") (name "unconnected-(D7-RA-Pad2)") (class "Default")
      (node (ref "D7") (pin "2") (pinfunction "RA_2") (pintype "passive+no_connect"))
    )
    (net (code "65") (name "unconnected-(D7-RK-Pad1)") (class "Default")
      (node (ref "D7") (pin "1") (pinfunction "RK_1") (pintype "passive+no_connect"))
    )
    (net (code "66") (name "unconnected-(J8-C1N-Pad5)") (class "Default")
      (node (ref "J8") (pin "5") (pinfunction "C1N_5") (pintype "passive+no_connect"))
    )
    (net (code "67") (name "unconnected-(J8-C1P-Pad4)") (class "Default")
      (node (ref "J8") (pin "4") (pinfunction "C1P_4") (pintype "passive+no_connect"))
    )
    (net (code "68") (name "unconnected-(J8-C2N-Pad3)") (class "Default")
      (node (ref "J8") (pin "3") (pinfunction "C2N_3") (pintype "passive+no_connect"))
    )
    (net (code "69") (name "unconnected-(J8-C2P-Pad2)") (class "Default")
      (node (ref "J8") (pin "2") (pinfunction "C2P_2") (pintype "passive+no_connect"))
    )
    (net (code "70") (name "unconnected-(J8-NC-Pad7)") (class "Default")
      (node (ref "J8") (pin "7") (pinfunction "NC_7") (pintype "passive+no_connect"))
    )
    (net (code "71") (name "unconnected-(J8-VBAT-Pad6)") (class "Default")
      (node (ref "J8") (pin "6") (pinfunction "VBAT_6") (pintype "passive+no_connect"))
    )
  )
)
